# Vapeix_mini_power.net
KiCad netlist of a schematic drawn in Altium Designer
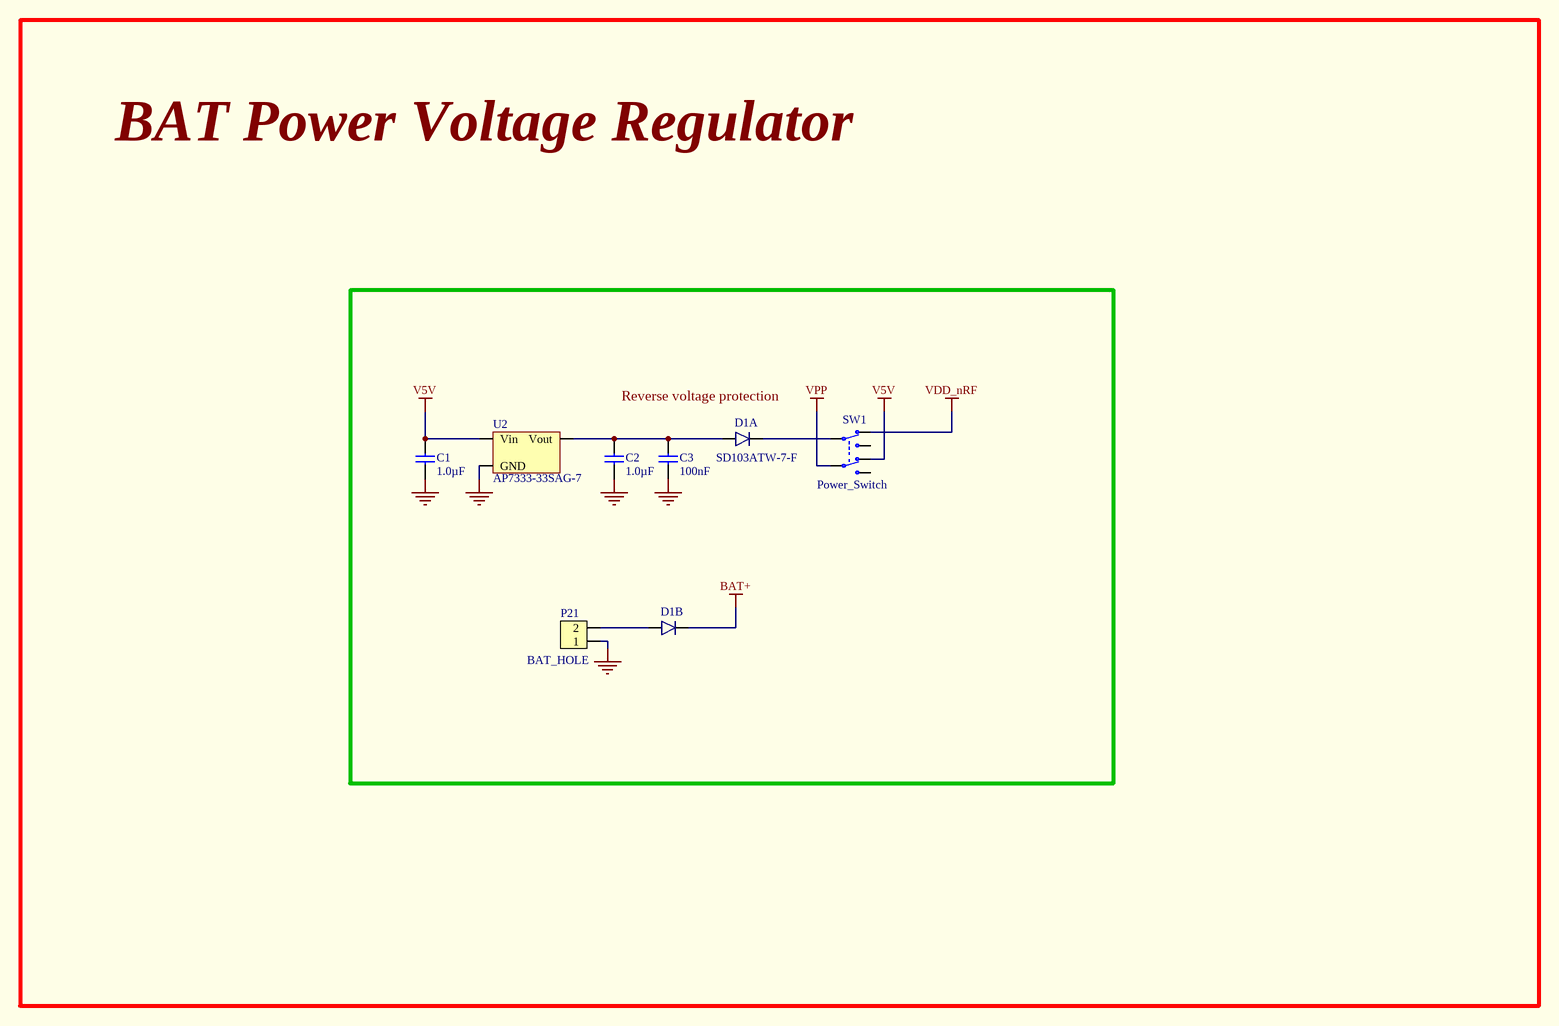
[diagram p0: Vapeix_mini_power.SchDoc]

(export (version "E")
  (design (tool "Eeschema 10.0.6"))
  (components
    (comp (ref "C1")
      (value "1.0µF")
      (footprint "CAPC1608X06L")
      (description "Capacitor, X7R, ±10%")
      (fields (field (name "PART NUMBER") "C0603-1µ0") (field (name "PUBLISHER") "Nordic Semiconductor"))
      (libsource (lib "Nordic Passive DB") (part "CAP"))
    )
    (comp (ref "C2")
      (value "1.0µF")
      (footprint "CAPC1608X06L")
      (description "Capacitor, X7R, ±10%")
      (fields (field (name "PART NUMBER") "C0603-1µ0") (field (name "PUBLISHER") "Nordic Semiconductor"))
      (libsource (lib "Nordic Passive DB") (part "CAP"))
    )
    (comp (ref "C3")
      (value "100nF")
      (footprint "CAPC1005X04L")
      (description "Capacitor, X7R, ±10%")
      (fields (field (name "PART NUMBER") "C0402-100n") (field (name "PUBLISHER") "Nordic Semiconductor"))
      (libsource (lib "Nordic Passive DB") (part "CAP"))
    )
    (comp (ref "D1")
      (value "SD103ATW-7-F")
      (footprint "SOT-363")
      (description "Surface Mount Schottky Barrier Diode Array")
      (fields
        (field (name "MANUFACTURER") "Diodes Incorporated")
        (field (name "2ND SOURCE PART NUMBER") "177-3507")
        (field (name "PUBLISHER") "Nordic Semiconductor")
      )
      (libsource (lib "pca10040") (part "D{colon}DIODE_3_IND"))
    )
    (comp (ref "P21")
      (value "BAT_HOLE")
      (footprint "LIST_ANG_1x2-SMD-2.54MM")
      (description "Pin List 1x2, 2.54mm (100mil), Right Angled, SMD")
      (fields
        (field (name "PART NUMBER") "Pin List Ang 1x2 SMD, 2.54mm")
        (field (name "2ND SOURCE PART NUMBER") "S1113E-02-ND")
        (field (name "PUBLISHER") "Nordic Semiconductor")
      )
      (libsource (lib "Nordic Passive DB") (part "CONN-2"))
    )
    (comp (ref "SW1")
      (value "Power_Switch")
      (footprint "JS202011SCQN")
      (description "SMD slide Switch (ON-ON)")
      (fields
        (field (name "PART NUMBER") "JS202011SCQN")
        (field (name "MANUFACTURER") "C&K Components")
        (field (name "PUBLISHER") "Nordic Semiconductor")
      )
      (libsource (lib "Nordic Discrete DB") (part "SW-DPDT"))
    )
    (comp (ref "U2")
      (value "AP7333-33SAG-7")
      (footprint "SOT-23A")
      (description "300mA, Low Quiescent Current, Fast Transient Low Dropout Linear Regulator")
      (fields
        (field (name "MANUFACTURER") "Diodes Incorporated")
        (field (name "PUBLISHER") "Nordic Semiconductor")
      )
      (libsource (lib "Nordic Active DB") (part "AP7333-XXSAG"))
    )
  )
  (nets
    (net (code "2") (name "BAT+") (class "Default")
      (node (ref "D1") (pin "2") (pinfunction "C2_2") (pintype "passive"))
    )
    (net (code "3") (name "GND") (class "Default")
      (node (ref "C1") (pin "1") (pinfunction "1_1") (pintype "passive"))
      (node (ref "C2") (pin "1") (pinfunction "1_1") (pintype "passive"))
      (node (ref "C3") (pin "1") (pinfunction "1_1") (pintype "passive"))
      (node (ref "P21") (pin "1") (pinfunction "1_1") (pintype "passive"))
      (node (ref "U2") (pin "3") (pinfunction "GND_3") (pintype "passive"))
    )
    (net (code "4") (name "Net-(D1A-A1)") (class "Default")
      (node (ref "C2") (pin "2") (pinfunction "2_2") (pintype "passive"))
      (node (ref "C3") (pin "2") (pinfunction "2_2") (pintype "passive"))
      (node (ref "D1") (pin "6") (pinfunction "A1_6") (pintype "passive"))
      (node (ref "U2") (pin "2") (pinfunction "Vout_2") (pintype "passive"))
    )
    (net (code "5") (name "Net-(D1A-C1)") (class "Default")
      (node (ref "D1") (pin "1") (pinfunction "C1_1") (pintype "passive"))
      (node (ref "SW1") (pin "2") (pinfunction "COM-1_2") (pintype "passive"))
    )
    (net (code "6") (name "Net-(D1B-A2)") (class "Default")
      (node (ref "D1") (pin "5") (pinfunction "A2_5") (pintype "passive"))
      (node (ref "P21") (pin "2") (pinfunction "2_2") (pintype "passive"))
    )
    (net (code "7") (name "V5V") (class "Default")
      (node (ref "C1") (pin "2") (pinfunction "2_2") (pintype "passive"))
      (node (ref "SW1") (pin "6") (pinfunction "N.C-2_6") (pintype "passive"))
      (node (ref "U2") (pin "1") (pinfunction "Vin_1") (pintype "passive"))
    )
    (net (code "8") (name "VDD_nRF") (class "Default")
      (node (ref "SW1") (pin "3") (pinfunction "N.C-1_3") (pintype "passive"))
    )
    (net (code "9") (name "VPP") (class "Default")
      (node (ref "SW1") (pin "5") (pinfunction "COM-2_5") (pintype "passive"))
    )
    (net (code "10") (name "unconnected-(SW1-N.O-1-Pad1)") (class "Default")
      (node (ref "SW1") (pin "1") (pinfunction "N.O-1_1") (pintype "passive"))
    )
    (net (code "11") (name "unconnected-(SW1-N.O-2-Pad4)") (class "Default")
      (node (ref "SW1") (pin "4") (pinfunction "N.O-2_4") (pintype "passive"))
    )
  )
)
